# mapleCUL_small-V11_02.net
KiCad netlist of a schematic drawn in EAGLE
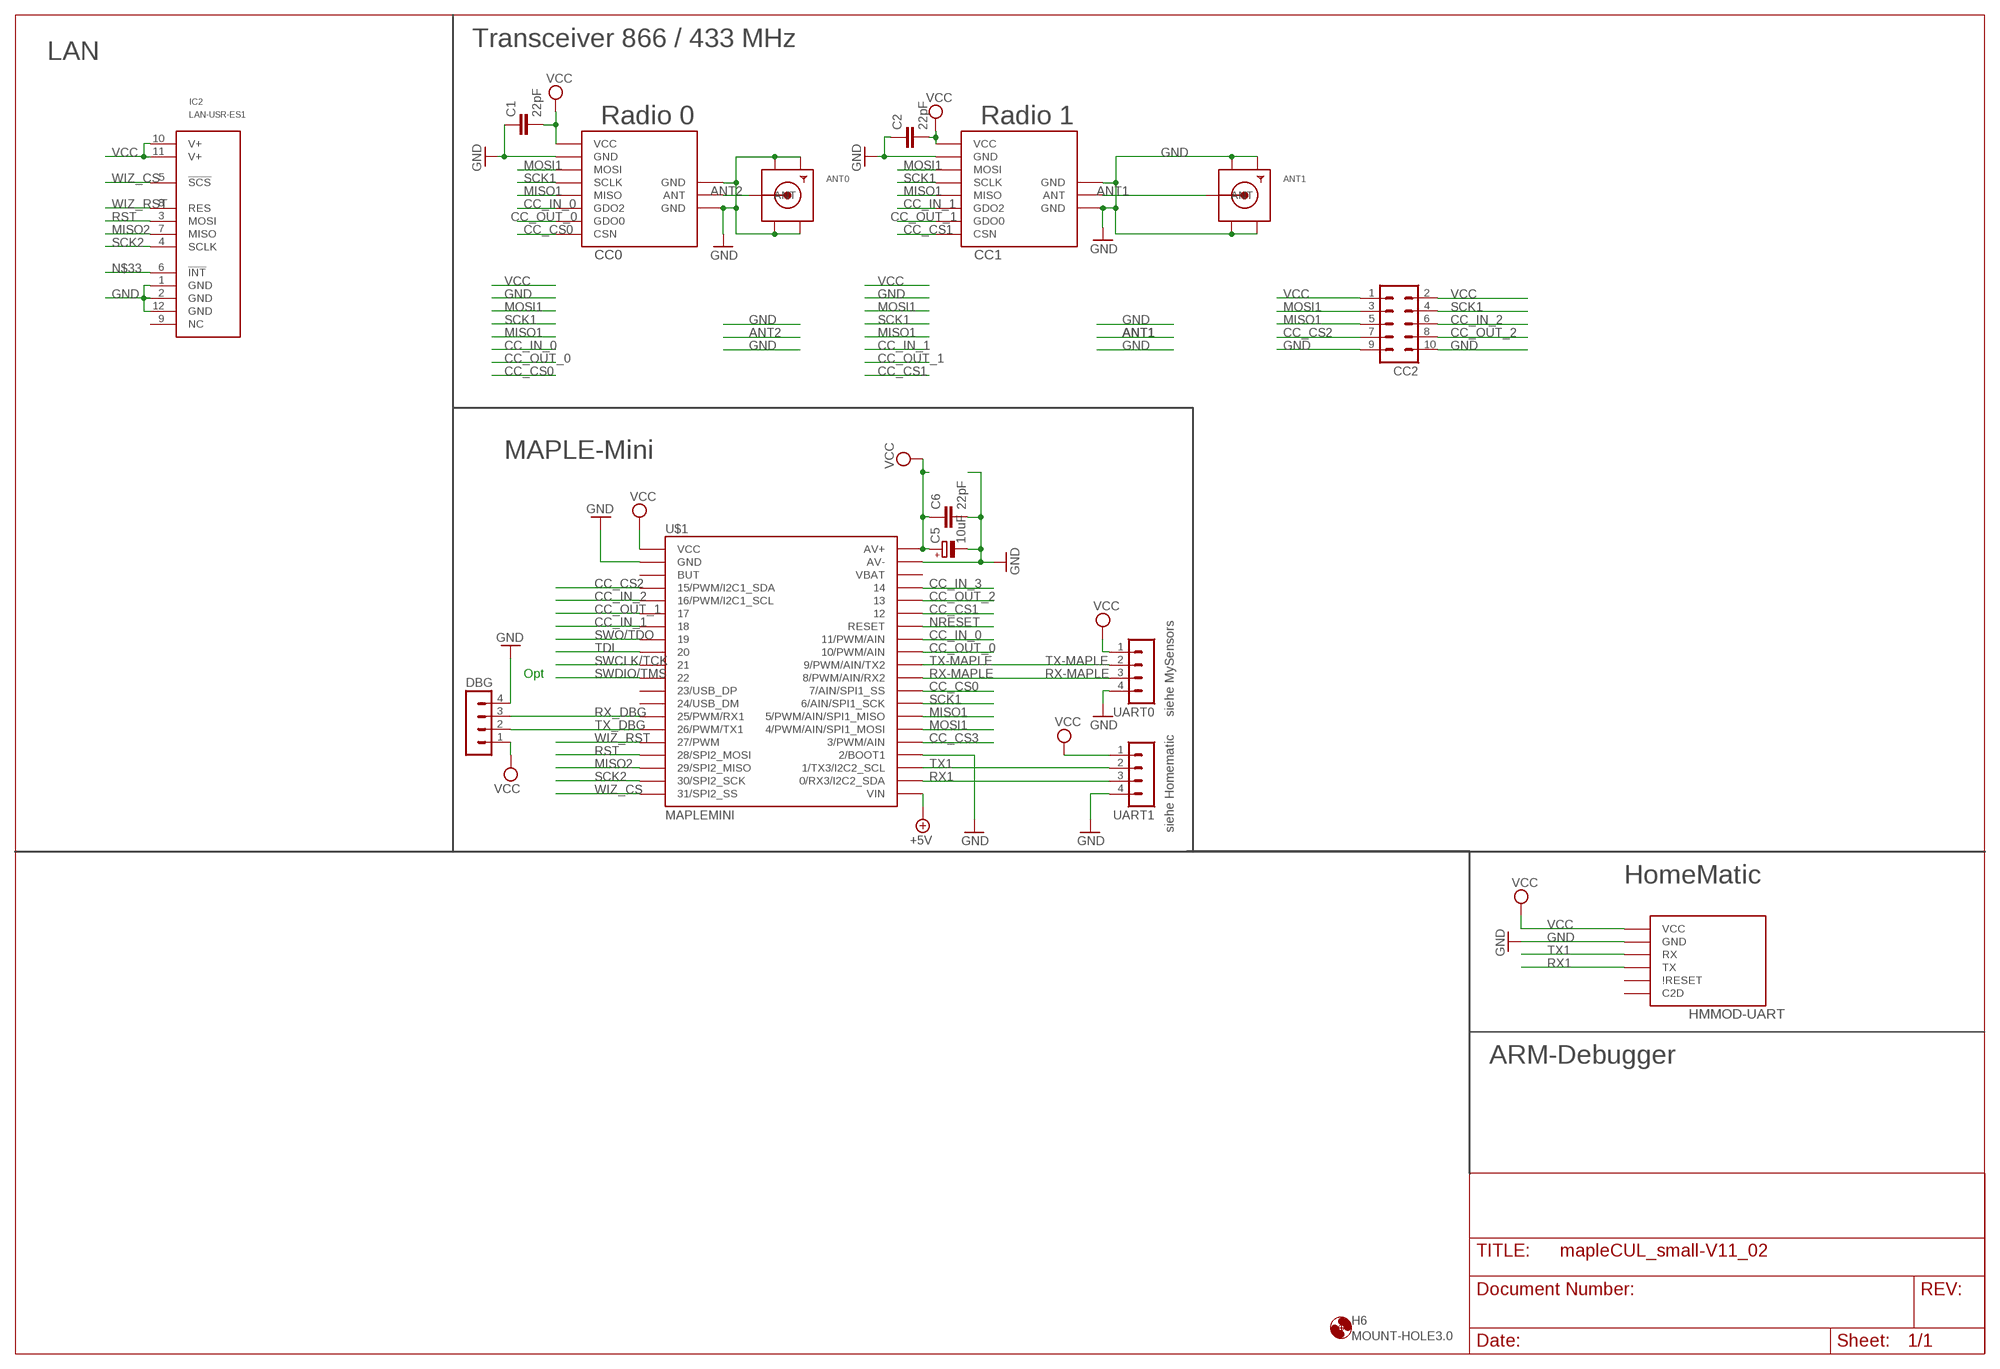
[diagram p0: schematic, sheet 1]

(export (version "E")
  (design (tool "Eeschema 10.0.6"))
  (components
    (comp (ref "ANT0")
      (value "SMACONNECTOR_EDGE_UFL")
      (footprint "eagle-import:SMA_EDGELAUNCH_UFL")
      (libsource (lib "eagle-import") (part "SMACONNECTOR_EDGE_UFL"))
    )
    (comp (ref "ANT1")
      (value "SMACONNECTOR_EDGE_UFL")
      (footprint "eagle-import:SMA_EDGELAUNCH_UFL")
      (libsource (lib "eagle-import") (part "SMACONNECTOR_EDGE_UFL"))
    )
    (comp (ref "C1")
      (value "22pF")
      (footprint "eagle-import:C0805")
      (libsource (lib "eagle-import") (part "C-EUC0805"))
    )
    (comp (ref "C2")
      (value "22pF")
      (footprint "eagle-import:C0805")
      (libsource (lib "eagle-import") (part "C-EUC0805"))
    )
    (comp (ref "C5")
      (value "10uF")
      (footprint "eagle-import:R_2012-12W")
      (libsource (lib "eagle-import") (part "CPOL-EUR/2012-12W"))
    )
    (comp (ref "C6")
      (value "22pF")
      (footprint "eagle-import:C0805")
      (libsource (lib "eagle-import") (part "C-EUC0805"))
    )
    (comp (ref "CC0")
      (value "CC1101")
      (footprint "eagle-import:CC1101_MODULE1_SMD")
      (libsource (lib "eagle-import") (part "CC1101_MODULE1SMD"))
    )
    (comp (ref "CC1")
      (value "CC1101_MODULE1SMD")
      (footprint "eagle-import:CC1101_MODULE1_SMD")
      (libsource (lib "eagle-import") (part "CC1101_MODULE1SMD"))
    )
    (comp (ref "CC2")
      (value "MA05-2")
      (footprint "eagle-import:MA05-2")
      (libsource (lib "eagle-import") (part "MA05-2"))
    )
    (comp (ref "DBG")
      (value "MA04-1")
      (footprint "eagle-import:MA04-1")
      (libsource (lib "eagle-import") (part "MA04-1"))
    )
    (comp (ref "H6")
      (value "MOUNT-HOLE3.0")
      (footprint "eagle-import:3,0")
      (libsource (lib "eagle-import") (part "MOUNT-HOLE3.0"))
    )
    (comp (ref "HMMOD-UART")
      (value "HM-MOD-UARTDIL")
      (footprint "eagle-import:HM-MOD-UART-DIL")
      (libsource (lib "eagle-import") (part "HM-MOD-UARTDIL"))
    )
    (comp (ref "IC2")
      (value "LAN-USR-ES1")
      (footprint "eagle-import:USR-ES1")
      (libsource (lib "eagle-import") (part "LAN-USR-ES1"))
    )
    (comp (ref "U$1")
      (value "MAPLEMINI")
      (footprint "eagle-import:20-DIP")
      (libsource (lib "eagle-import") (part "MAPLEMINI"))
    )
    (comp (ref "UART0")
      (value "MA04-1")
      (footprint "eagle-import:MA04-1")
      (libsource (lib "eagle-import") (part "MA04-1"))
    )
    (comp (ref "UART1")
      (value "MA04-1")
      (footprint "eagle-import:MA04-1")
      (libsource (lib "eagle-import") (part "MA04-1"))
    )
  )
  (nets
    (net (code "1") (name "+5V") (class "Default")
      (node (ref "U$1") (pin "21") (pinfunction "VIN_21") (pintype "bidirectional"))
    )
    (net (code "2") (name "/ANT1") (class "Default")
      (node (ref "ANT1") (pin "P") (pinfunction "ANT_P") (pintype "bidirectional"))
      (node (ref "CC1") (pin "ANT") (pinfunction "ANT_ANT") (pintype "output"))
    )
    (net (code "3") (name "/ANT2") (class "Default")
      (node (ref "ANT0") (pin "P") (pinfunction "ANT_P") (pintype "bidirectional"))
      (node (ref "CC0") (pin "ANT") (pinfunction "ANT_ANT") (pintype "output"))
    )
    (net (code "4") (name "/CC_CS0") (class "Default")
      (node (ref "CC0") (pin "CSN") (pinfunction "CSN_CSN") (pintype "bidirectional"))
      (node (ref "U$1") (pin "29") (pinfunction "7/AIN/SPI1_SS_29") (pintype "bidirectional"))
    )
    (net (code "5") (name "/CC_CS1") (class "Default")
      (node (ref "CC1") (pin "CSN") (pinfunction "CSN_CSN") (pintype "bidirectional"))
      (node (ref "U$1") (pin "35") (pinfunction "12_35") (pintype "bidirectional"))
    )
    (net (code "6") (name "/CC_CS2") (class "Default")
      (node (ref "CC2") (pin "7") (pinfunction "7_7") (pintype "passive"))
      (node (ref "U$1") (pin "4") (pinfunction "15/PWM/I2C1_SDA_4") (pintype "bidirectional"))
    )
    (net (code "7") (name "/CC_CS3") (class "Default")
      (node (ref "U$1") (pin "25") (pinfunction "3/PWM/AIN_25") (pintype "bidirectional"))
    )
    (net (code "8") (name "/CC_IN_0") (class "Default")
      (node (ref "CC0") (pin "GDO2") (pinfunction "GDO2_GDO2") (pintype "bidirectional"))
      (node (ref "U$1") (pin "33") (pinfunction "11/PWM/AIN_33") (pintype "bidirectional"))
    )
    (net (code "9") (name "/CC_IN_1") (class "Default")
      (node (ref "CC1") (pin "GDO2") (pinfunction "GDO2_GDO2") (pintype "bidirectional"))
      (node (ref "U$1") (pin "7") (pinfunction "18_7") (pintype "bidirectional"))
    )
    (net (code "10") (name "/CC_IN_2") (class "Default")
      (node (ref "CC2") (pin "6") (pinfunction "6_6") (pintype "passive"))
      (node (ref "U$1") (pin "5") (pinfunction "16/PWM/I2C1_SCL_5") (pintype "bidirectional"))
    )
    (net (code "11") (name "/CC_IN_3") (class "Default")
      (node (ref "U$1") (pin "37") (pinfunction "14_37") (pintype "bidirectional"))
    )
    (net (code "12") (name "/CC_OUT_0") (class "Default")
      (node (ref "CC0") (pin "GDO0") (pinfunction "GDO0_GDO0") (pintype "bidirectional"))
      (node (ref "U$1") (pin "32") (pinfunction "10/PWM/AIN_32") (pintype "bidirectional"))
    )
    (net (code "13") (name "/CC_OUT_1") (class "Default")
      (node (ref "CC1") (pin "GDO0") (pinfunction "GDO0_GDO0") (pintype "bidirectional"))
      (node (ref "U$1") (pin "6") (pinfunction "17_6") (pintype "bidirectional"))
    )
    (net (code "14") (name "/CC_OUT_2") (class "Default")
      (node (ref "CC2") (pin "8") (pinfunction "8_8") (pintype "passive"))
      (node (ref "U$1") (pin "36") (pinfunction "13_36") (pintype "bidirectional"))
    )
    (net (code "15") (name "/MISO1") (class "Default")
      (node (ref "CC0") (pin "MISO") (pinfunction "MISO_MISO") (pintype "bidirectional"))
      (node (ref "CC1") (pin "MISO") (pinfunction "MISO_MISO") (pintype "bidirectional"))
      (node (ref "CC2") (pin "5") (pinfunction "5_5") (pintype "passive"))
      (node (ref "U$1") (pin "27") (pinfunction "5/PWM/AIN/SPI1_MISO_27") (pintype "bidirectional"))
    )
    (net (code "16") (name "/MISO2") (class "Default")
      (node (ref "IC2") (pin "7") (pinfunction "MISO_7") (pintype "bidirectional"))
      (node (ref "U$1") (pin "18") (pinfunction "29/SPI2_MISO_18") (pintype "bidirectional"))
    )
    (net (code "17") (name "/MOSI1") (class "Default")
      (node (ref "CC0") (pin "MOSI") (pinfunction "MOSI_MOSI") (pintype "bidirectional"))
      (node (ref "CC1") (pin "MOSI") (pinfunction "MOSI_MOSI") (pintype "bidirectional"))
      (node (ref "CC2") (pin "3") (pinfunction "3_3") (pintype "passive"))
      (node (ref "U$1") (pin "26") (pinfunction "4/PWM/AIN/SPI1_MOSI_26") (pintype "bidirectional"))
    )
    (net (code "18") (name "/N$33") (class "Default")
      (node (ref "IC2") (pin "6") (pinfunction "~{INT}_6") (pintype "output"))
    )
    (net (code "19") (name "/NRESET") (class "Default")
      (node (ref "U$1") (pin "34") (pinfunction "RESET_34") (pintype "bidirectional"))
    )
    (net (code "20") (name "/RST") (class "Default")
      (node (ref "IC2") (pin "3") (pinfunction "MOSI_3") (pintype "bidirectional"))
      (node (ref "U$1") (pin "17") (pinfunction "28/SPI2_MOSI_17") (pintype "bidirectional"))
    )
    (net (code "21") (name "/RX-MAPLE") (class "Default")
      (node (ref "U$1") (pin "30") (pinfunction "8/PWM/AIN/RX2_30") (pintype "bidirectional"))
      (node (ref "UART0") (pin "3") (pinfunction "3_3") (pintype "passive"))
    )
    (net (code "22") (name "/RX1") (class "Default")
      (node (ref "HMMOD-UART") (pin "5") (pinfunction "TX_5") (pintype "bidirectional"))
      (node (ref "U$1") (pin "22") (pinfunction "0/RX3/I2C2_SDA_22") (pintype "bidirectional"))
      (node (ref "UART1") (pin "3") (pinfunction "3_3") (pintype "passive"))
    )
    (net (code "23") (name "/RX_DBG") (class "Default")
      (node (ref "DBG") (pin "3") (pinfunction "3_3") (pintype "passive"))
      (node (ref "U$1") (pin "14") (pinfunction "25/PWM/RX1_14") (pintype "bidirectional"))
    )
    (net (code "24") (name "/SCK1") (class "Default")
      (node (ref "CC0") (pin "SCLK") (pinfunction "SCLK_SCLK") (pintype "bidirectional"))
      (node (ref "CC1") (pin "SCLK") (pinfunction "SCLK_SCLK") (pintype "bidirectional"))
      (node (ref "CC2") (pin "4") (pinfunction "4_4") (pintype "passive"))
      (node (ref "U$1") (pin "28") (pinfunction "6/AIN/SPI1_SCK_28") (pintype "bidirectional"))
    )
    (net (code "25") (name "/SCK2") (class "Default")
      (node (ref "IC2") (pin "4") (pinfunction "SCLK_4") (pintype "input"))
      (node (ref "U$1") (pin "19") (pinfunction "30/SPI2_SCK_19") (pintype "bidirectional"))
    )
    (net (code "26") (name "/SWCLK{slash}TCK") (class "Default")
      (node (ref "U$1") (pin "10") (pinfunction "21_10") (pintype "bidirectional"))
    )
    (net (code "27") (name "/SWDIO{slash}TMS") (class "Default")
      (node (ref "U$1") (pin "11") (pinfunction "22_11") (pintype "bidirectional"))
    )
    (net (code "28") (name "/SWO{slash}TDO") (class "Default")
      (node (ref "U$1") (pin "8") (pinfunction "19_8") (pintype "bidirectional"))
    )
    (net (code "29") (name "/TDI") (class "Default")
      (node (ref "U$1") (pin "9") (pinfunction "20_9") (pintype "bidirectional"))
    )
    (net (code "30") (name "/TX-MAPLE") (class "Default")
      (node (ref "U$1") (pin "31") (pinfunction "9/PWM/AIN/TX2_31") (pintype "bidirectional"))
      (node (ref "UART0") (pin "2") (pinfunction "2_2") (pintype "passive"))
    )
    (net (code "31") (name "/TX1") (class "Default")
      (node (ref "HMMOD-UART") (pin "6") (pinfunction "RX_6") (pintype "bidirectional"))
      (node (ref "U$1") (pin "23") (pinfunction "1/TX3/I2C2_SCL_23") (pintype "bidirectional"))
      (node (ref "UART1") (pin "2") (pinfunction "2_2") (pintype "passive"))
    )
    (net (code "32") (name "/TX_DBG") (class "Default")
      (node (ref "DBG") (pin "2") (pinfunction "2_2") (pintype "passive"))
      (node (ref "U$1") (pin "15") (pinfunction "26/PWM/TX1_15") (pintype "bidirectional"))
    )
    (net (code "33") (name "/WIZ_CS") (class "Default")
      (node (ref "IC2") (pin "5") (pinfunction "~{SCS}_5") (pintype "input"))
      (node (ref "U$1") (pin "20") (pinfunction "31/SPI2_SS_20") (pintype "bidirectional"))
    )
    (net (code "34") (name "/WIZ_RST") (class "Default")
      (node (ref "IC2") (pin "8") (pinfunction "RES_8") (pintype "input"))
      (node (ref "U$1") (pin "16") (pinfunction "27/PWM_16") (pintype "bidirectional"))
    )
    (net (code "35") (name "GND") (class "Default")
      (node (ref "ANT0") (pin "GND@1") (pinfunction "GND1_GND@1") (pintype "power_in"))
      (node (ref "ANT0") (pin "GND@2") (pinfunction "GND2_GND@2") (pintype "power_in"))
      (node (ref "ANT0") (pin "GND@3") (pinfunction "GND3_GND@3") (pintype "power_in"))
      (node (ref "ANT0") (pin "GND@4") (pinfunction "GND4_GND@4") (pintype "power_in"))
      (node (ref "ANT1") (pin "GND@1") (pinfunction "GND1_GND@1") (pintype "power_in"))
      (node (ref "ANT1") (pin "GND@2") (pinfunction "GND2_GND@2") (pintype "power_in"))
      (node (ref "ANT1") (pin "GND@3") (pinfunction "GND3_GND@3") (pintype "power_in"))
      (node (ref "ANT1") (pin "GND@4") (pinfunction "GND4_GND@4") (pintype "power_in"))
      (node (ref "C1") (pin "1") (pinfunction "1_1") (pintype "passive"))
      (node (ref "C2") (pin "1") (pinfunction "1_1") (pintype "passive"))
      (node (ref "C5") (pin "-") (pinfunction "-_-") (pintype "passive"))
      (node (ref "C6") (pin "2") (pinfunction "2_2") (pintype "passive"))
      (node (ref "CC0") (pin "GND@0") (pinfunction "GND_GND@0") (pintype "power_in"))
      (node (ref "CC0") (pin "GND@1") (pinfunction "GND_GND@1") (pintype "power_in"))
      (node (ref "CC0") (pin "GND@2") (pinfunction "GND_GND@2") (pintype "power_in"))
      (node (ref "CC1") (pin "GND@0") (pinfunction "GND_GND@0") (pintype "power_in"))
      (node (ref "CC1") (pin "GND@1") (pinfunction "GND_GND@1") (pintype "power_in"))
      (node (ref "CC1") (pin "GND@2") (pinfunction "GND_GND@2") (pintype "power_in"))
      (node (ref "CC2") (pin "10") (pinfunction "10_10") (pintype "passive"))
      (node (ref "CC2") (pin "9") (pinfunction "9_9") (pintype "passive"))
      (node (ref "DBG") (pin "4") (pinfunction "4_4") (pintype "passive"))
      (node (ref "HMMOD-UART") (pin "2") (pinfunction "GND_2") (pintype "power_in"))
      (node (ref "IC2") (pin "1") (pinfunction "GND_1") (pintype "power_in"))
      (node (ref "IC2") (pin "12") (pinfunction "GND_12") (pintype "power_in"))
      (node (ref "IC2") (pin "2") (pinfunction "GND_2") (pintype "power_in"))
      (node (ref "U$1") (pin "2") (pinfunction "GND_2") (pintype "bidirectional"))
      (node (ref "U$1") (pin "24") (pinfunction "2/BOOT1_24") (pintype "bidirectional"))
      (node (ref "U$1") (pin "39") (pinfunction "AV-_39") (pintype "bidirectional"))
      (node (ref "UART0") (pin "4") (pinfunction "4_4") (pintype "passive"))
      (node (ref "UART1") (pin "4") (pinfunction "4_4") (pintype "passive"))
    )
    (net (code "36") (name "VCC") (class "Default")
      (node (ref "C1") (pin "2") (pinfunction "2_2") (pintype "passive"))
      (node (ref "C2") (pin "2") (pinfunction "2_2") (pintype "passive"))
      (node (ref "C5") (pin "+") (pinfunction "+_+") (pintype "passive"))
      (node (ref "C6") (pin "1") (pinfunction "1_1") (pintype "passive"))
      (node (ref "CC0") (pin "VCC") (pinfunction "VCC_VCC") (pintype "power_in"))
      (node (ref "CC1") (pin "VCC") (pinfunction "VCC_VCC") (pintype "power_in"))
      (node (ref "CC2") (pin "1") (pinfunction "1_1") (pintype "passive"))
      (node (ref "CC2") (pin "2") (pinfunction "2_2") (pintype "passive"))
      (node (ref "DBG") (pin "1") (pinfunction "1_1") (pintype "passive"))
      (node (ref "HMMOD-UART") (pin "1") (pinfunction "VCC_1") (pintype "power_in"))
      (node (ref "IC2") (pin "10") (pinfunction "V+_10") (pintype "power_in"))
      (node (ref "IC2") (pin "11") (pinfunction "V+_11") (pintype "power_in"))
      (node (ref "U$1") (pin "1") (pinfunction "VCC_1") (pintype "bidirectional"))
      (node (ref "U$1") (pin "40") (pinfunction "AV+_40") (pintype "bidirectional"))
      (node (ref "UART0") (pin "1") (pinfunction "1_1") (pintype "passive"))
      (node (ref "UART1") (pin "1") (pinfunction "1_1") (pintype "passive"))
    )
    (net (code "37") (name "unconnected-(HMMOD-UART-C2D-Pad3)") (class "Default")
      (node (ref "HMMOD-UART") (pin "3") (pinfunction "C2D_3") (pintype "bidirectional"))
    )
    (net (code "38") (name "unconnected-(HMMOD-UART-\\~{RESET}-Pad4)") (class "Default")
      (node (ref "HMMOD-UART") (pin "4") (pinfunction "\\~{RESET}_4") (pintype "bidirectional"))
    )
    (net (code "39") (name "unconnected-(IC2-NC-Pad9)") (class "Default")
      (node (ref "IC2") (pin "9") (pinfunction "NC_9") (pintype "no_connect"))
    )
    (net (code "40") (name "unconnected-(U$1-23{slash}USB_DP-Pad12)") (class "Default")
      (node (ref "U$1") (pin "12") (pinfunction "23/USB_DP_12") (pintype "bidirectional"))
    )
    (net (code "41") (name "unconnected-(U$1-24{slash}USB_DM-Pad13)") (class "Default")
      (node (ref "U$1") (pin "13") (pinfunction "24/USB_DM_13") (pintype "bidirectional"))
    )
    (net (code "42") (name "unconnected-(U$1-BUT-Pad3)") (class "Default")
      (node (ref "U$1") (pin "3") (pinfunction "BUT_3") (pintype "bidirectional"))
    )
    (net (code "43") (name "unconnected-(U$1-VBAT-Pad38)") (class "Default")
      (node (ref "U$1") (pin "38") (pinfunction "VBAT_38") (pintype "bidirectional"))
    )
  )
)
